# Main-v5_1.net
KiCad netlist of a schematic drawn in EAGLE
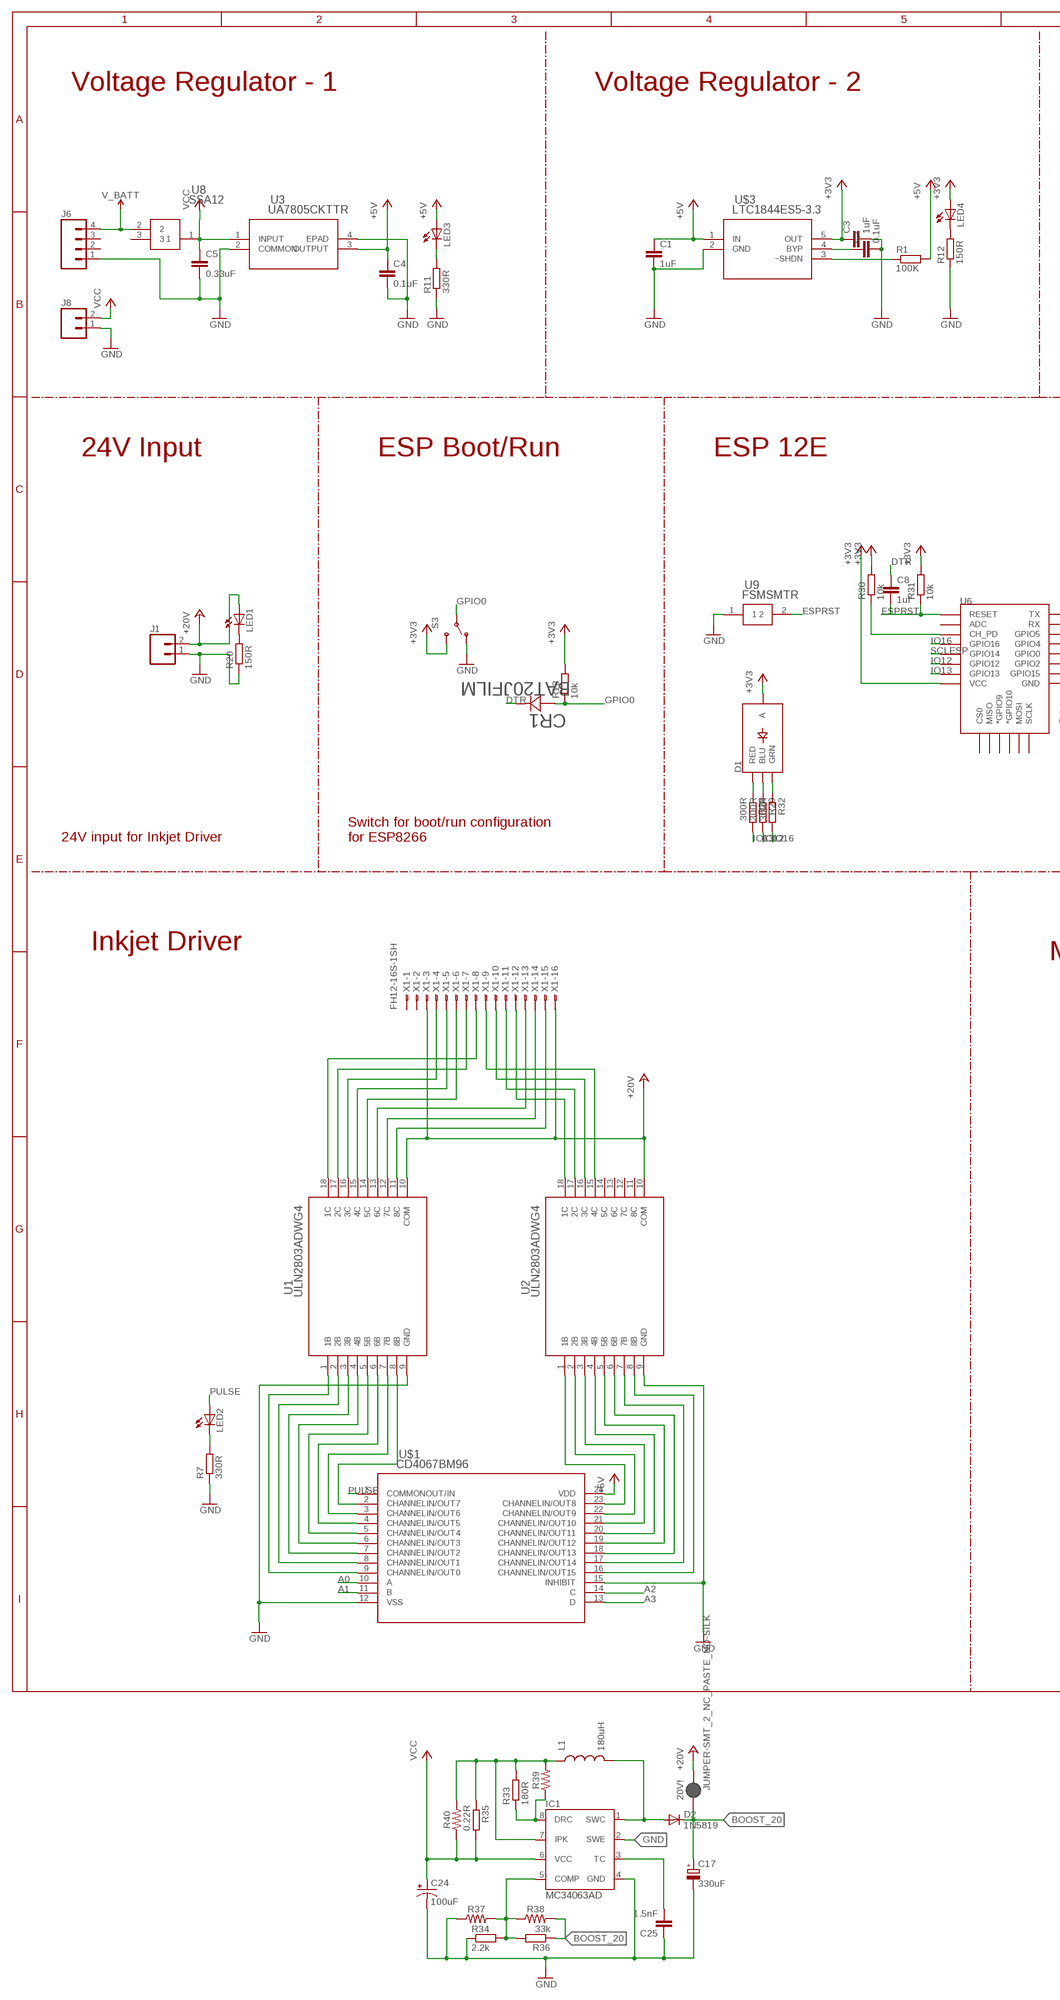
[diagram p0: schematic, sheet 1, part 1 of 2]
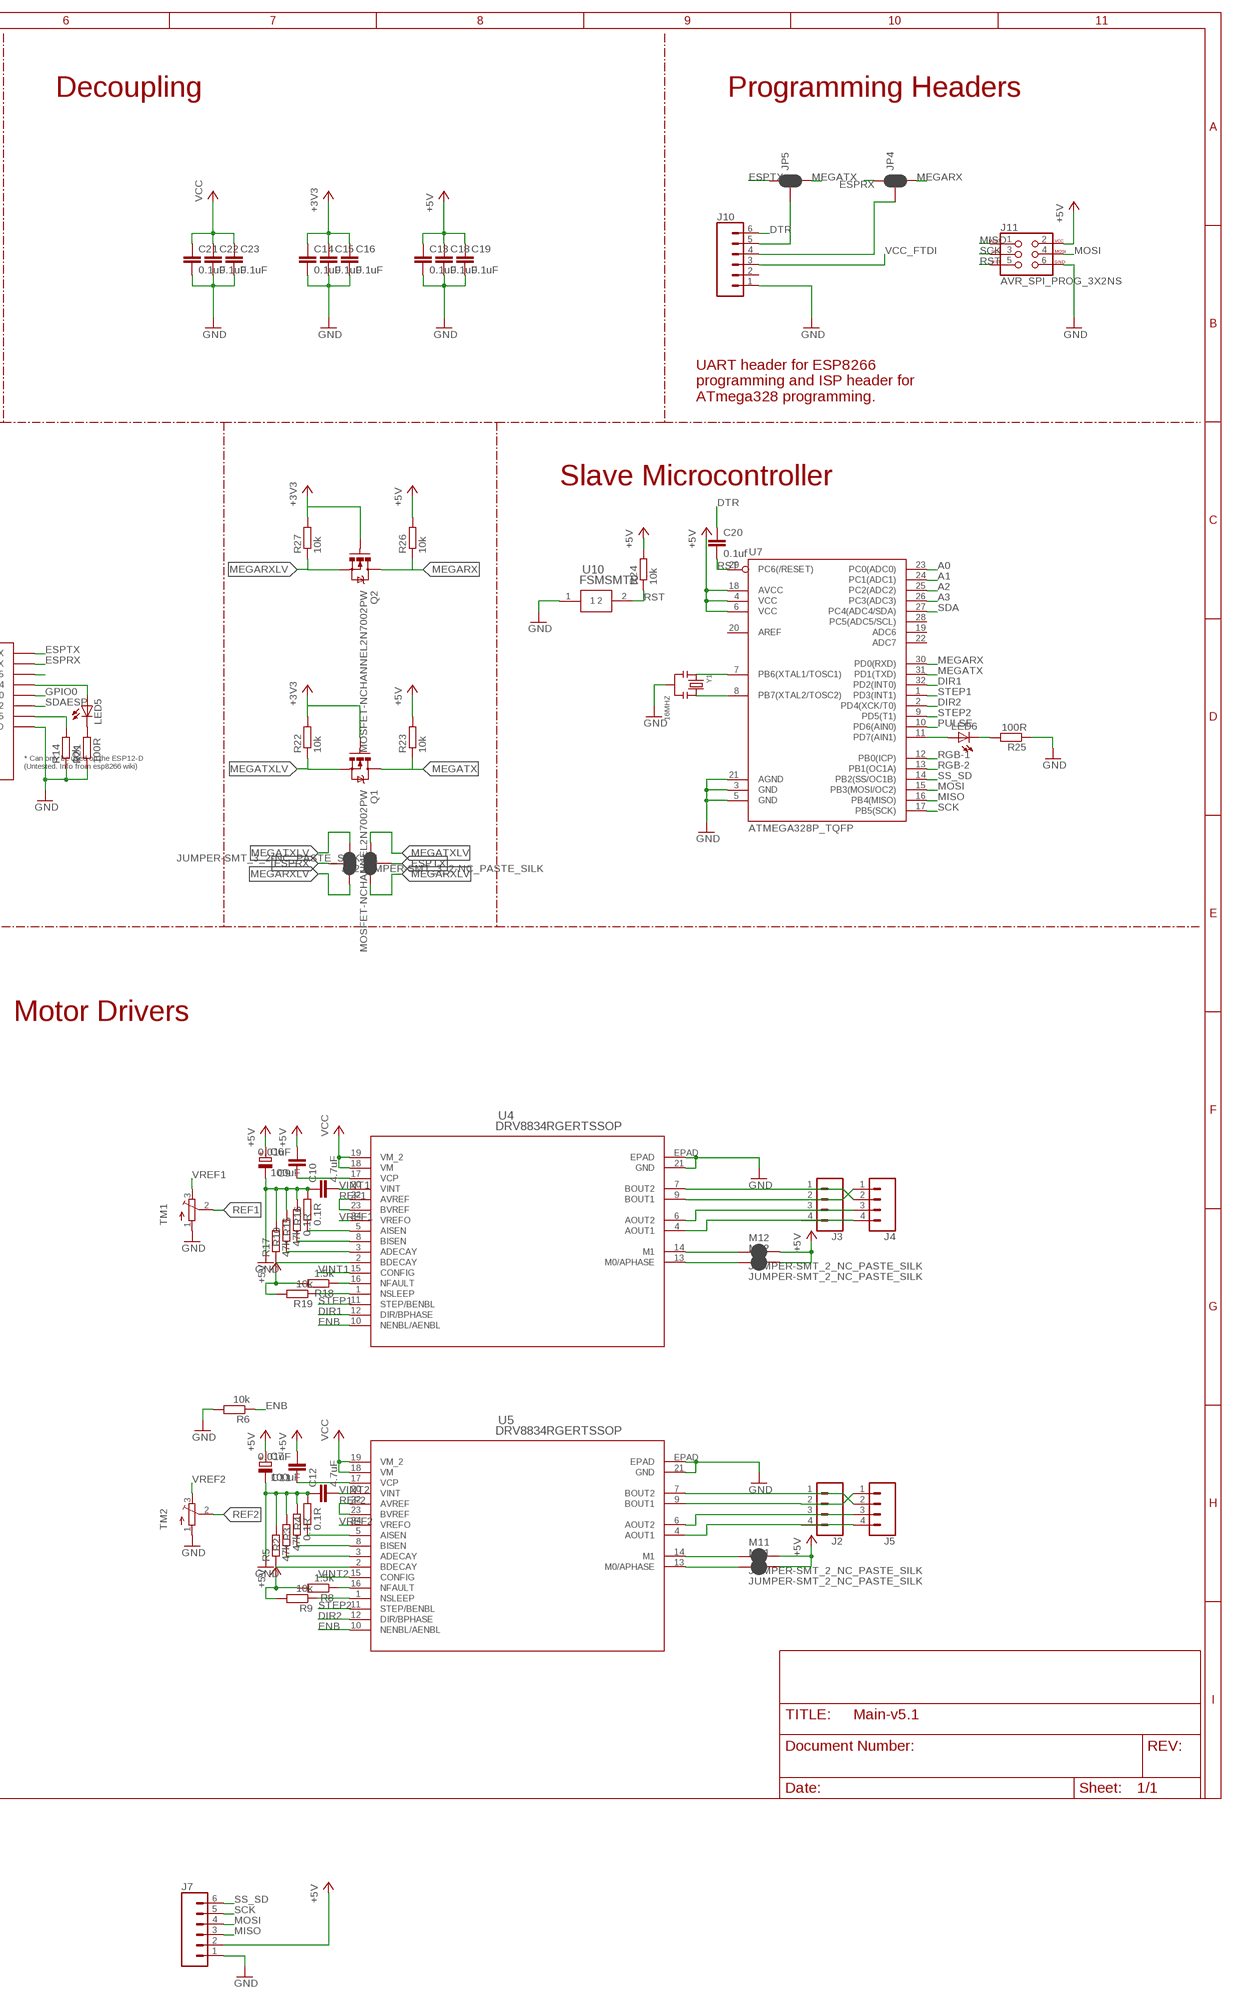
[diagram p1: schematic, sheet 1, part 2 of 2]

(export (version "E")
  (design (tool "Eeschema 10.0.6"))
  (components
    (comp (ref "20V!")
      (value "JUMPER-SMT_2_NC_PASTE_NO-SILK")
      (footprint "eagle-import:SMT-JUMPER_2_NC_PASTE_NO-SILK")
      (libsource (lib "eagle-import") (part "JUMPER-SMT_2_NC_PASTE_NO-SILK"))
    )
    (comp (ref "C1")
      (value "1uF")
      (footprint "eagle-import:C0603")
      (libsource (lib "eagle-import") (part "C-EUC0603"))
    )
    (comp (ref "C2")
      (value "0.1uF")
      (footprint "eagle-import:C0603")
      (libsource (lib "eagle-import") (part "C-EUC0603"))
    )
    (comp (ref "C3")
      (value "1uF")
      (footprint "eagle-import:C0603")
      (libsource (lib "eagle-import") (part "C-EUC0603"))
    )
    (comp (ref "C4")
      (value "0.1uF")
      (footprint "eagle-import:C0603")
      (libsource (lib "eagle-import") (part "C-EUC0603"))
    )
    (comp (ref "C5")
      (value "0.33uF")
      (footprint "eagle-import:C0603")
      (libsource (lib "eagle-import") (part "C-EUC0603"))
    )
    (comp (ref "C6")
      (value "100uF")
      (footprint "eagle-import:E5-5")
      (libsource (lib "eagle-import") (part "CPOL-EUE5-5"))
    )
    (comp (ref "C7")
      (value "100uF")
      (footprint "eagle-import:E5-5")
      (libsource (lib "eagle-import") (part "CPOL-EUE5-5"))
    )
    (comp (ref "C8")
      (value "1uf")
      (footprint "eagle-import:C0603")
      (libsource (lib "eagle-import") (part "resistor_348_C-EUC0603"))
    )
    (comp (ref "C9")
      (value "0.01uF")
      (footprint "eagle-import:C0603K")
      (libsource (lib "eagle-import") (part "resistor_348_C-EUC0603K"))
    )
    (comp (ref "C10")
      (value "4.7uF")
      (footprint "eagle-import:C0603K")
      (libsource (lib "eagle-import") (part "resistor_348_C-EUC0603K"))
    )
    (comp (ref "C11")
      (value "0.01uF")
      (footprint "eagle-import:C0603K")
      (libsource (lib "eagle-import") (part "resistor_348_C-EUC0603K"))
    )
    (comp (ref "C12")
      (value "4.7uF")
      (footprint "eagle-import:C0603K")
      (libsource (lib "eagle-import") (part "resistor_348_C-EUC0603K"))
    )
    (comp (ref "C13")
      (value "0.1uF")
      (footprint "eagle-import:C0603")
      (libsource (lib "eagle-import") (part "C-EUC0603"))
    )
    (comp (ref "C14")
      (value "0.1uF")
      (footprint "eagle-import:C0603")
      (libsource (lib "eagle-import") (part "C-EUC0603"))
    )
    (comp (ref "C15")
      (value "0.1uF")
      (footprint "eagle-import:C0603")
      (libsource (lib "eagle-import") (part "C-EUC0603"))
    )
    (comp (ref "C16")
      (value "0.1uF")
      (footprint "eagle-import:C0603")
      (libsource (lib "eagle-import") (part "C-EUC0603"))
    )
    (comp (ref "C17")
      (value "330uF")
      (footprint "eagle-import:153CLV-1010")
      (libsource (lib "eagle-import") (part "resistor_348_CPOL-EU153CLV-1010"))
    )
    (comp (ref "C18")
      (value "0.1uF")
      (footprint "eagle-import:C0603")
      (libsource (lib "eagle-import") (part "C-EUC0603"))
    )
    (comp (ref "C19")
      (value "0.1uF")
      (footprint "eagle-import:C0603")
      (libsource (lib "eagle-import") (part "C-EUC0603"))
    )
    (comp (ref "C20")
      (value "0.1uf")
      (footprint "eagle-import:C0603")
      (libsource (lib "eagle-import") (part "resistor_348_C-EUC0603"))
    )
    (comp (ref "C21")
      (value "0.1uF")
      (footprint "eagle-import:C0603")
      (libsource (lib "eagle-import") (part "C-EUC0603"))
    )
    (comp (ref "C22")
      (value "0.1uF")
      (footprint "eagle-import:C0603")
      (libsource (lib "eagle-import") (part "C-EUC0603"))
    )
    (comp (ref "C23")
      (value "0.1uF")
      (footprint "eagle-import:C0603")
      (libsource (lib "eagle-import") (part "C-EUC0603"))
    )
    (comp (ref "C24")
      (value "100uF")
      (footprint "eagle-import:CPOL-RADIAL-5MM-10MM")
      (libsource (lib "eagle-import") (part "1000UF-RADIAL-5MM-25V-20%"))
    )
    (comp (ref "C25")
      (value "1.5nF")
      (footprint "eagle-import:C0603K")
      (libsource (lib "eagle-import") (part "resistor_348_C-EUC0603K"))
    )
    (comp (ref "CR1")
      (value "BAT20JFILM")
      (footprint "eagle-import:SOD-323")
      (libsource (lib "eagle-import") (part "BAT20JFILM"))
    )
    (comp (ref "D1")
      (value "LED-RGB-CASMD")
      (footprint "eagle-import:LED-TRICOLOR-SMD")
      (libsource (lib "eagle-import") (part "LED-RGB-CASMD"))
    )
    (comp (ref "D2")
      (value "1N5819")
      (footprint "eagle-import:SOD123")
      (libsource (lib "eagle-import") (part "1N5819"))
    )
    (comp (ref "IC1")
      (value "MC34063AD")
      (footprint "eagle-import:SO08")
      (fields (field (name "MF") "ON Semiconductor") (field (name "MP") "MC34063A"))
      (libsource (lib "eagle-import") (part "MC34063AD"))
    )
    (comp (ref "J1")
      (value "CONN_02")
      (footprint "eagle-import:1X02")
      (libsource (lib "eagle-import") (part "SparkFun-Connectors_513_CONN_02"))
    )
    (comp (ref "J2")
      (value "CONN_04")
      (footprint "eagle-import:1X04")
      (libsource (lib "eagle-import") (part "CONN_04"))
    )
    (comp (ref "J3")
      (value "CONN_04")
      (footprint "eagle-import:1X04")
      (libsource (lib "eagle-import") (part "CONN_04"))
    )
    (comp (ref "J4")
      (value "CONN_04")
      (footprint "eagle-import:1X04")
      (libsource (lib "eagle-import") (part "CONN_04"))
    )
    (comp (ref "J5")
      (value "CONN_04")
      (footprint "eagle-import:1X04")
      (libsource (lib "eagle-import") (part "CONN_04"))
    )
    (comp (ref "J6")
      (value "CONN_04")
      (footprint "eagle-import:1X04")
      (libsource (lib "eagle-import") (part "CONN_04"))
    )
    (comp (ref "J7")
      (value "CONN_06SILK_FEMALE_PTH")
      (footprint "eagle-import:1X06")
      (libsource (lib "eagle-import") (part "CONN_06SILK_FEMALE_PTH"))
    )
    (comp (ref "J8")
      (value "CONN_02")
      (footprint "eagle-import:1X02")
      (libsource (lib "eagle-import") (part "CONN_02"))
    )
    (comp (ref "J10")
      (value "CONN_06NO_SILK_NO_POP")
      (footprint "eagle-import:1X06_NO_SILK")
      (libsource (lib "eagle-import") (part "SparkFun-Connectors_513_CONN_06NO_SILK_NO_POP"))
    )
    (comp (ref "J11")
      (value "AVR_SPI_PROG_3X2NS")
      (footprint "eagle-import:2X3-NS")
      (libsource (lib "eagle-import") (part "AVR_SPI_PROG_3X2NS"))
    )
    (comp (ref "JP1")
      (value "JUMPER-SMT_3_2-NC_PASTE_SILK")
      (footprint "eagle-import:SMT-JUMPER_3_2-NC_PASTE_SILK")
      (libsource (lib "eagle-import") (part "JUMPER-SMT_3_2-NC_PASTE_SILK"))
    )
    (comp (ref "JP2")
      (value "JUMPER-SMT_3_2-NC_PASTE_SILK")
      (footprint "eagle-import:SMT-JUMPER_3_2-NC_PASTE_SILK")
      (libsource (lib "eagle-import") (part "JUMPER-SMT_3_2-NC_PASTE_SILK"))
    )
    (comp (ref "JP4")
      (value "JUMPER-SMT_3_2-NC_PASTE_SILK")
      (footprint "eagle-import:SMT-JUMPER_3_2-NC_PASTE_SILK")
      (libsource (lib "eagle-import") (part "JUMPER-SMT_3_2-NC_PASTE_SILK"))
    )
    (comp (ref "JP5")
      (value "JUMPER-SMT_3_2-NC_PASTE_SILK")
      (footprint "eagle-import:SMT-JUMPER_3_2-NC_PASTE_SILK")
      (libsource (lib "eagle-import") (part "JUMPER-SMT_3_2-NC_PASTE_SILK"))
    )
    (comp (ref "L1")
      (value "180uH")
      (footprint "eagle-import:CR54")
      (libsource (lib "eagle-import") (part "INDUCTORCR54"))
    )
    (comp (ref "LED1")
      (value "LEDSML0603")
      (footprint "eagle-import:SML0603")
      (libsource (lib "eagle-import") (part "LEDSML0603"))
    )
    (comp (ref "LED2")
      (value "LEDSML0603")
      (footprint "eagle-import:SML0603")
      (libsource (lib "eagle-import") (part "LEDSML0603"))
    )
    (comp (ref "LED3")
      (value "LEDSML0603")
      (footprint "eagle-import:SML0603")
      (libsource (lib "eagle-import") (part "LEDSML0603"))
    )
    (comp (ref "LED4")
      (value "LEDSML0603")
      (footprint "eagle-import:SML0603")
      (libsource (lib "eagle-import") (part "LEDSML0603"))
    )
    (comp (ref "LED5")
      (value "LEDSML0603")
      (footprint "eagle-import:SML0603")
      (libsource (lib "eagle-import") (part "LEDSML0603"))
    )
    (comp (ref "LED6")
      (value "LEDSML0603")
      (footprint "eagle-import:SML0603")
      (libsource (lib "eagle-import") (part "LEDSML0603"))
    )
    (comp (ref "M01")
      (value "JUMPER-SMT_2_NC_PASTE_SILK")
      (footprint "eagle-import:SMT-JUMPER_2_NC_PASTE_SILK")
      (libsource (lib "eagle-import") (part "JUMPER-SMT_2_NC_PASTE_SILK"))
    )
    (comp (ref "M02")
      (value "JUMPER-SMT_2_NC_PASTE_SILK")
      (footprint "eagle-import:SMT-JUMPER_2_NC_PASTE_SILK")
      (libsource (lib "eagle-import") (part "JUMPER-SMT_2_NC_PASTE_SILK"))
    )
    (comp (ref "M11")
      (value "JUMPER-SMT_2_NC_PASTE_SILK")
      (footprint "eagle-import:SMT-JUMPER_2_NC_PASTE_SILK")
      (libsource (lib "eagle-import") (part "JUMPER-SMT_2_NC_PASTE_SILK"))
    )
    (comp (ref "M12")
      (value "JUMPER-SMT_2_NC_PASTE_SILK")
      (footprint "eagle-import:SMT-JUMPER_2_NC_PASTE_SILK")
      (libsource (lib "eagle-import") (part "JUMPER-SMT_2_NC_PASTE_SILK"))
    )
    (comp (ref "Q1")
      (value "MOSFET-NCHANNEL2N7002PW")
      (footprint "eagle-import:SOT323")
      (libsource (lib "eagle-import") (part "MOSFET-NCHANNEL2N7002PW"))
    )
    (comp (ref "Q2")
      (value "MOSFET-NCHANNEL2N7002PW")
      (footprint "eagle-import:SOT323")
      (libsource (lib "eagle-import") (part "MOSFET-NCHANNEL2N7002PW"))
    )
    (comp (ref "R1")
      (value "100K")
      (footprint "eagle-import:R0603")
      (libsource (lib "eagle-import") (part "R-EU_R0603"))
    )
    (comp (ref "R2")
      (value "47k")
      (footprint "eagle-import:R0402")
      (libsource (lib "eagle-import") (part "resistor_348_R-EU_R0402"))
    )
    (comp (ref "R3")
      (value "0.1R")
      (footprint "eagle-import:R0402")
      (libsource (lib "eagle-import") (part "resistor_348_R-EU_R0402"))
    )
    (comp (ref "R4")
      (value "0.1R")
      (footprint "eagle-import:R0402")
      (libsource (lib "eagle-import") (part "resistor_348_R-EU_R0402"))
    )
    (comp (ref "R5")
      (value "47k")
      (footprint "eagle-import:R0402")
      (libsource (lib "eagle-import") (part "resistor_348_R-EU_R0402"))
    )
    (comp (ref "R6")
      (value "10k")
      (footprint "eagle-import:R0402")
      (libsource (lib "eagle-import") (part "resistor_348_R-EU_R0402"))
    )
    (comp (ref "R7")
      (value "330R")
      (footprint "eagle-import:R0603")
      (libsource (lib "eagle-import") (part "R-EU_R0603"))
    )
    (comp (ref "R8")
      (value "1.5k")
      (footprint "eagle-import:R0402")
      (libsource (lib "eagle-import") (part "resistor_348_R-EU_R0402"))
    )
    (comp (ref "R9")
      (value "10k")
      (footprint "eagle-import:R0402")
      (libsource (lib "eagle-import") (part "resistor_348_R-EU_R0402"))
    )
    (comp (ref "R10")
      (value "47k")
      (footprint "eagle-import:R0402")
      (libsource (lib "eagle-import") (part "resistor_348_R-EU_R0402"))
    )
    (comp (ref "R11")
      (value "330R")
      (footprint "eagle-import:R0603")
      (libsource (lib "eagle-import") (part "R-EU_R0603"))
    )
    (comp (ref "R12")
      (value "150R")
      (footprint "eagle-import:R0603")
      (libsource (lib "eagle-import") (part "R-EU_R0603"))
    )
    (comp (ref "R13")
      (value "10k")
      (footprint "eagle-import:R0603")
      (libsource (lib "eagle-import") (part "R-EU_R0603"))
    )
    (comp (ref "R14")
      (value "10k")
      (footprint "eagle-import:R0603")
      (libsource (lib "eagle-import") (part "R-EU_R0603"))
    )
    (comp (ref "R15")
      (value "0.1R")
      (footprint "eagle-import:R0402")
      (libsource (lib "eagle-import") (part "resistor_348_R-EU_R0402"))
    )
    (comp (ref "R16")
      (value "0.1R")
      (footprint "eagle-import:R0402")
      (libsource (lib "eagle-import") (part "resistor_348_R-EU_R0402"))
    )
    (comp (ref "R17")
      (value "47k")
      (footprint "eagle-import:R0402")
      (libsource (lib "eagle-import") (part "resistor_348_R-EU_R0402"))
    )
    (comp (ref "R18")
      (value "1.5k")
      (footprint "eagle-import:R0402")
      (libsource (lib "eagle-import") (part "resistor_348_R-EU_R0402"))
    )
    (comp (ref "R19")
      (value "10k")
      (footprint "eagle-import:R0402")
      (libsource (lib "eagle-import") (part "resistor_348_R-EU_R0402"))
    )
    (comp (ref "R20")
      (value "150R")
      (footprint "eagle-import:R0603")
      (libsource (lib "eagle-import") (part "R-EU_R0603"))
    )
    (comp (ref "R21")
      (value "100R")
      (footprint "eagle-import:R0603")
      (libsource (lib "eagle-import") (part "R-EU_R0603"))
    )
    (comp (ref "R22")
      (value "10k")
      (footprint "eagle-import:R0603")
      (libsource (lib "eagle-import") (part "R-EU_R0603"))
    )
    (comp (ref "R23")
      (value "10k")
      (footprint "eagle-import:R0603")
      (libsource (lib "eagle-import") (part "R-EU_R0603"))
    )
    (comp (ref "R24")
      (value "10k")
      (footprint "eagle-import:R0603")
      (libsource (lib "eagle-import") (part "R-EU_R0603"))
    )
    (comp (ref "R25")
      (value "100R")
      (footprint "eagle-import:R0603")
      (libsource (lib "eagle-import") (part "R-EU_R0603"))
    )
    (comp (ref "R26")
      (value "10k")
      (footprint "eagle-import:R0603")
      (libsource (lib "eagle-import") (part "R-EU_R0603"))
    )
    (comp (ref "R27")
      (value "10k")
      (footprint "eagle-import:R0603")
      (libsource (lib "eagle-import") (part "R-EU_R0603"))
    )
    (comp (ref "R28")
      (value "300R")
      (footprint "eagle-import:R0603")
      (libsource (lib "eagle-import") (part "R-EU_R0603"))
    )
    (comp (ref "R29")
      (value "300R")
      (footprint "eagle-import:R0603")
      (libsource (lib "eagle-import") (part "R-EU_R0603"))
    )
    (comp (ref "R30")
      (value "10k")
      (footprint "eagle-import:R0603")
      (libsource (lib "eagle-import") (part "R-EU_R0603"))
    )
    (comp (ref "R31")
      (value "10k")
      (footprint "eagle-import:R0603")
      (libsource (lib "eagle-import") (part "R-EU_R0603"))
    )
    (comp (ref "R32")
      (value "300R")
      (footprint "eagle-import:R0603")
      (libsource (lib "eagle-import") (part "R-EU_R0603"))
    )
    (comp (ref "R33")
      (value "180R")
      (footprint "eagle-import:R0603")
      (libsource (lib "eagle-import") (part "R-EU_R0603"))
    )
    (comp (ref "R34")
      (value "2.2k")
      (footprint "eagle-import:R0603")
      (libsource (lib "eagle-import") (part "R-EU_R0603"))
    )
    (comp (ref "R35")
      (value "0.22R")
      (footprint "eagle-import:R0603")
      (libsource (lib "eagle-import") (part "R-EU_R0603"))
    )
    (comp (ref "R36")
      (value "33k")
      (footprint "eagle-import:R0603")
      (libsource (lib "eagle-import") (part "R-EU_R0603"))
    )
    (comp (ref "R37")
      (value "RESISTORAXIAL-0.3")
      (footprint "eagle-import:AXIAL-0.3")
      (libsource (lib "eagle-import") (part "RESISTORAXIAL-0.3"))
    )
    (comp (ref "R38")
      (value "RESISTORAXIAL-0.3")
      (footprint "eagle-import:AXIAL-0.3")
      (libsource (lib "eagle-import") (part "RESISTORAXIAL-0.3"))
    )
    (comp (ref "R39")
      (value "RESISTORAXIAL-0.3")
      (footprint "eagle-import:AXIAL-0.3")
      (libsource (lib "eagle-import") (part "RESISTORAXIAL-0.3"))
    )
    (comp (ref "R40")
      (value "RESISTORAXIAL-0.3")
      (footprint "eagle-import:AXIAL-0.3")
      (libsource (lib "eagle-import") (part "RESISTORAXIAL-0.3"))
    )
    (comp (ref "S3")
      (value "SWITCH-SPDT-SMD-A")
      (footprint "eagle-import:SWITCH-SPST-SMD-A")
      (libsource (lib "eagle-import") (part "SWITCH-SPDT-SMD-A"))
    )
    (comp (ref "TM1")
      (value "TRIMPOTTC33X")
      (footprint "eagle-import:TC33X")
      (libsource (lib "eagle-import") (part "TRIMPOTTC33X"))
    )
    (comp (ref "TM2")
      (value "TRIMPOTTC33X")
      (footprint "eagle-import:TC33X")
      (libsource (lib "eagle-import") (part "TRIMPOTTC33X"))
    )
    (comp (ref "U$1")
      (value "CD4067BM96")
      (footprint "eagle-import:DW24")
      (fields (field (name "MANUFACTURER_PART_NUMBER") "CD4067B_DW_24"))
      (libsource (lib "eagle-import") (part "CD4067BM96"))
    )
    (comp (ref "U$3")
      (value "LTC1844ES5-3.3")
      (footprint "eagle-import:TSOT-23_S5")
      (libsource (lib "eagle-import") (part "LTC1844ES5-3.3"))
    )
    (comp (ref "U1")
      (value "ULN2803ADWG4")
      (footprint "eagle-import:DW18")
      (libsource (lib "eagle-import") (part "ULN2803ADWG4"))
    )
    (comp (ref "U2")
      (value "ULN2803ADWG4")
      (footprint "eagle-import:DW18")
      (libsource (lib "eagle-import") (part "ULN2803ADWG4"))
    )
    (comp (ref "U3")
      (value "UA7805CKTTR")
      (footprint "eagle-import:KTT3_6P22X6P6")
      (libsource (lib "eagle-import") (part "UA7805CKTTR"))
    )
    (comp (ref "U4")
      (value "DRV8834RGERTSSOP")
      (footprint "eagle-import:PWP_24")
      (libsource (lib "eagle-import") (part "DRV8834RGERTSSOP"))
    )
    (comp (ref "U5")
      (value "DRV8834RGERTSSOP")
      (footprint "eagle-import:PWP_24")
      (libsource (lib "eagle-import") (part "DRV8834RGERTSSOP"))
    )
    (comp (ref "U6")
      (value "ESP12ESMD")
      (footprint "eagle-import:ESP12E-SMD")
      (libsource (lib "eagle-import") (part "ESP12ESMD"))
    )
    (comp (ref "U7")
      (value "ATMEGA328P_TQFP")
      (footprint "eagle-import:TQFP32-08")
      (libsource (lib "eagle-import") (part "ATMEGA328P_TQFP"))
    )
    (comp (ref "U8")
      (value "SSA12")
      (footprint "eagle-import:SWSIP3-P98")
      (libsource (lib "eagle-import") (part "SSA12"))
    )
    (comp (ref "U9")
      (value "FSMSMTR")
      (footprint "eagle-import:SWITCH_FSMSMTR")
      (libsource (lib "eagle-import") (part "FSMSMTR"))
    )
    (comp (ref "U10")
      (value "FSMSMTR")
      (footprint "eagle-import:SWITCH_FSMSMTR")
      (libsource (lib "eagle-import") (part "FSMSMTR"))
    )
    (comp (ref "X1")
      (value "FH12-16S-1SH")
      (footprint "eagle-import:FH12-16S-1SH")
      (libsource (lib "eagle-import") (part "FH12-16S-1SH"))
    )
    (comp (ref "Y1")
      (value "16MHZ")
      (footprint "eagle-import:X3-SMD-3.6X1.3X0.8MM")
      (fields (field (name "MPN") "CSTCE16M0V53-R0"))
      (libsource (lib "eagle-import") (part "SMD-RESONATOR-16MHZ-15PF-0.5%-40R(3P-3.2X1.3MM)"))
    )
  )
  (nets
    (net (code "1") (name "+3V3") (class "Default")
      (node (ref "C14") (pin "1") (pinfunction "1_1") (pintype "passive"))
      (node (ref "C15") (pin "1") (pinfunction "1_1") (pintype "passive"))
      (node (ref "C16") (pin "1") (pinfunction "1_1") (pintype "passive"))
      (node (ref "C3") (pin "1") (pinfunction "1_1") (pintype "passive"))
      (node (ref "D1") (pin "A") (pinfunction "A_A") (pintype "bidirectional"))
      (node (ref "LED4") (pin "A") (pinfunction "A_A") (pintype "passive"))
      (node (ref "Q1") (pin "1") (pinfunction "G_1") (pintype "passive"))
      (node (ref "Q2") (pin "1") (pinfunction "G_1") (pintype "passive"))
      (node (ref "R13") (pin "2") (pinfunction "2_2") (pintype "passive"))
      (node (ref "R22") (pin "2") (pinfunction "2_2") (pintype "passive"))
      (node (ref "R27") (pin "2") (pinfunction "2_2") (pintype "passive"))
      (node (ref "R30") (pin "2") (pinfunction "2_2") (pintype "passive"))
      (node (ref "R31") (pin "2") (pinfunction "2_2") (pintype "passive"))
      (node (ref "S3") (pin "3") (pinfunction "S_3") (pintype "passive"))
      (node (ref "U$3") (pin "5") (pinfunction "OUT_5") (pintype "passive"))
      (node (ref "U6") (pin "VCC") (pinfunction "VCC_VCC") (pintype "bidirectional"))
    )
    (net (code "2") (name "+5V") (class "Default")
      (node (ref "C1") (pin "1") (pinfunction "1_1") (pintype "passive"))
      (node (ref "C11") (pin "2") (pinfunction "2_2") (pintype "passive"))
      (node (ref "C13") (pin "1") (pinfunction "1_1") (pintype "passive"))
      (node (ref "C18") (pin "1") (pinfunction "1_1") (pintype "passive"))
      (node (ref "C19") (pin "1") (pinfunction "1_1") (pintype "passive"))
      (node (ref "C4") (pin "1") (pinfunction "1_1") (pintype "passive"))
      (node (ref "C6") (pin "+") (pinfunction "+_+") (pintype "passive"))
      (node (ref "C7") (pin "+") (pinfunction "+_+") (pintype "passive"))
      (node (ref "C9") (pin "2") (pinfunction "2_2") (pintype "passive"))
      (node (ref "J11") (pin "2") (pinfunction "2_2") (pintype "passive"))
      (node (ref "J7") (pin "2") (pinfunction "2_2") (pintype "passive"))
      (node (ref "LED3") (pin "A") (pinfunction "A_A") (pintype "passive"))
      (node (ref "M01") (pin "2") (pinfunction "2_2") (pintype "passive"))
      (node (ref "M02") (pin "2") (pinfunction "2_2") (pintype "passive"))
      (node (ref "M11") (pin "2") (pinfunction "2_2") (pintype "passive"))
      (node (ref "M12") (pin "2") (pinfunction "2_2") (pintype "passive"))
      (node (ref "R1") (pin "2") (pinfunction "2_2") (pintype "passive"))
      (node (ref "R18") (pin "2") (pinfunction "2_2") (pintype "passive"))
      (node (ref "R19") (pin "2") (pinfunction "2_2") (pintype "passive"))
      (node (ref "R23") (pin "2") (pinfunction "2_2") (pintype "passive"))
      (node (ref "R24") (pin "2") (pinfunction "2_2") (pintype "passive"))
      (node (ref "R26") (pin "2") (pinfunction "2_2") (pintype "passive"))
      (node (ref "R8") (pin "2") (pinfunction "2_2") (pintype "passive"))
      (node (ref "R9") (pin "2") (pinfunction "2_2") (pintype "passive"))
      (node (ref "U$1") (pin "24") (pinfunction "VDD_24") (pintype "power_in"))
      (node (ref "U$3") (pin "1") (pinfunction "IN_1") (pintype "passive"))
      (node (ref "U3") (pin "3") (pinfunction "OUTPUT_3") (pintype "output"))
      (node (ref "U7") (pin "18") (pinfunction "AVCC_18") (pintype "bidirectional"))
      (node (ref "U7") (pin "4") (pinfunction "VCC_4") (pintype "bidirectional"))
      (node (ref "U7") (pin "6") (pinfunction "VCC_6") (pintype "bidirectional"))
    )
    (net (code "3") (name "+20V") (class "Default")
      (node (ref "20V!") (pin "2") (pinfunction "2_2") (pintype "passive"))
      (node (ref "J1") (pin "2") (pinfunction "2_2") (pintype "passive"))
      (node (ref "LED1") (pin "A") (pinfunction "A_A") (pintype "passive"))
      (node (ref "U1") (pin "10") (pinfunction "COM_10") (pintype "passive"))
      (node (ref "U2") (pin "10") (pinfunction "COM_10") (pintype "passive"))
      (node (ref "X1") (pin "16") (pinfunction "1_16") (pintype "passive"))
      (node (ref "X1") (pin "3") (pinfunction "1_3") (pintype "passive"))
    )
    (net (code "4") (name "/A0") (class "Default")
      (node (ref "U$1") (pin "10") (pinfunction "A_10") (pintype "passive"))
      (node (ref "U7") (pin "23") (pinfunction "PC0(ADC0)_23") (pintype "bidirectional"))
    )
    (net (code "5") (name "/A1") (class "Default")
      (node (ref "U$1") (pin "11") (pinfunction "B_11") (pintype "passive"))
      (node (ref "U7") (pin "24") (pinfunction "PC1(ADC1)_24") (pintype "bidirectional"))
    )
    (net (code "6") (name "/A2") (class "Default")
      (node (ref "U$1") (pin "14") (pinfunction "C_14") (pintype "passive"))
      (node (ref "U7") (pin "25") (pinfunction "PC2(ADC2)_25") (pintype "bidirectional"))
    )
    (net (code "7") (name "/A3") (class "Default")
      (node (ref "U$1") (pin "13") (pinfunction "D_13") (pintype "passive"))
      (node (ref "U7") (pin "26") (pinfunction "PC3(ADC3)_26") (pintype "bidirectional"))
    )
    (net (code "8") (name "/DIR1") (class "Default")
      (node (ref "U4") (pin "12") (pinfunction "DIR/BPHASE_12") (pintype "input"))
      (node (ref "U7") (pin "32") (pinfunction "PD2(INT0)_32") (pintype "bidirectional"))
    )
    (net (code "9") (name "/DIR2") (class "Default")
      (node (ref "U5") (pin "12") (pinfunction "DIR/BPHASE_12") (pintype "input"))
      (node (ref "U7") (pin "2") (pinfunction "PD4(XCK/T0)_2") (pintype "bidirectional"))
    )
    (net (code "10") (name "/DTR") (class "Default")
      (node (ref "C20") (pin "1") (pinfunction "1_1") (pintype "passive"))
      (node (ref "C8") (pin "1") (pinfunction "1_1") (pintype "passive"))
      (node (ref "CR1") (pin "1") (pinfunction "11_1") (pintype "passive"))
      (node (ref "J10") (pin "6") (pinfunction "6_6") (pintype "passive"))
    )
    (net (code "11") (name "/ENB") (class "Default")
      (node (ref "R6") (pin "1") (pinfunction "1_1") (pintype "passive"))
      (node (ref "U4") (pin "10") (pinfunction "NENBL/AENBL_10") (pintype "input"))
      (node (ref "U5") (pin "10") (pinfunction "NENBL/AENBL_10") (pintype "input"))
    )
    (net (code "12") (name "/ESPRST") (class "Default")
      (node (ref "C8") (pin "2") (pinfunction "2_2") (pintype "passive"))
      (node (ref "R31") (pin "1") (pinfunction "1_1") (pintype "passive"))
      (node (ref "U6") (pin "RESET") (pinfunction "RESET_RESET") (pintype "bidirectional"))
      (node (ref "U9") (pin "2") (pinfunction "2_2") (pintype "passive"))
    )
    (net (code "13") (name "/GPIO0") (class "Default")
      (node (ref "CR1") (pin "2") (pinfunction "22_2") (pintype "passive"))
      (node (ref "R13") (pin "1") (pinfunction "1_1") (pintype "passive"))
      (node (ref "S3") (pin "2") (pinfunction "P_2") (pintype "passive"))
      (node (ref "U6") (pin "GPIO0") (pinfunction "GPIO0_GPIO0") (pintype "bidirectional"))
    )
    (net (code "14") (name "/IO12") (class "Default")
      (node (ref "R29") (pin "2") (pinfunction "2_2") (pintype "passive"))
      (node (ref "U6") (pin "GPIO12") (pinfunction "GPIO12_GPIO12") (pintype "bidirectional"))
    )
    (net (code "15") (name "/IO13") (class "Default")
      (node (ref "R28") (pin "2") (pinfunction "2_2") (pintype "passive"))
      (node (ref "U6") (pin "GPIO13") (pinfunction "GPIO13_GPIO13") (pintype "bidirectional"))
    )
    (net (code "16") (name "/IO16") (class "Default")
      (node (ref "R32") (pin "2") (pinfunction "2_2") (pintype "passive"))
      (node (ref "U6") (pin "GPIO16") (pinfunction "GPIO16_GPIO16") (pintype "bidirectional"))
    )
    (net (code "17") (name "/MISO") (class "Default")
      (node (ref "J11") (pin "1") (pinfunction "1_1") (pintype "passive"))
      (node (ref "J7") (pin "3") (pinfunction "3_3") (pintype "passive"))
      (node (ref "U7") (pin "16") (pinfunction "PB4(MISO)_16") (pintype "bidirectional"))
    )
    (net (code "18") (name "/MOSI") (class "Default")
      (node (ref "J11") (pin "4") (pinfunction "4_4") (pintype "passive"))
      (node (ref "J7") (pin "4") (pinfunction "4_4") (pintype "passive"))
      (node (ref "U7") (pin "15") (pinfunction "PB3(MOSI/OC2)_15") (pintype "bidirectional"))
    )
    (net (code "19") (name "/PULSE") (class "Default")
      (node (ref "LED2") (pin "A") (pinfunction "A_A") (pintype "passive"))
      (node (ref "U$1") (pin "1") (pinfunction "COMMONOUT/IN_1") (pintype "bidirectional"))
      (node (ref "U7") (pin "10") (pinfunction "PD6(AIN0)_10") (pintype "bidirectional"))
    )
    (net (code "20") (name "/RGB-1") (class "Default")
      (node (ref "U7") (pin "12") (pinfunction "PB0(ICP)_12") (pintype "bidirectional"))
    )
    (net (code "21") (name "/RGB-2") (class "Default")
      (node (ref "U7") (pin "13") (pinfunction "PB1(OC1A)_13") (pintype "bidirectional"))
    )
    (net (code "22") (name "/RST") (class "Default")
      (node (ref "C20") (pin "2") (pinfunction "2_2") (pintype "passive"))
      (node (ref "J11") (pin "5") (pinfunction "5_5") (pintype "passive"))
      (node (ref "R24") (pin "1") (pinfunction "1_1") (pintype "passive"))
      (node (ref "U10") (pin "2") (pinfunction "2_2") (pintype "passive"))
      (node (ref "U7") (pin "29") (pinfunction "PC6(/RESET)_29") (pintype "bidirectional"))
    )
    (net (code "23") (name "/SCK") (class "Default")
      (node (ref "J11") (pin "3") (pinfunction "3_3") (pintype "passive"))
      (node (ref "J7") (pin "5") (pinfunction "5_5") (pintype "passive"))
      (node (ref "U7") (pin "17") (pinfunction "PB5(SCK)_17") (pintype "bidirectional"))
    )
    (net (code "24") (name "/SCLESP") (class "Default")
      (node (ref "U6") (pin "GPIO14") (pinfunction "GPIO14_GPIO14") (pintype "bidirectional"))
    )
    (net (code "25") (name "/SDA") (class "Default")
      (node (ref "U7") (pin "27") (pinfunction "PC4(ADC4/SDA)_27") (pintype "bidirectional"))
    )
    (net (code "26") (name "/SDAESP") (class "Default")
      (node (ref "U6") (pin "GPIO2") (pinfunction "GPIO2_GPIO2") (pintype "bidirectional"))
    )
    (net (code "27") (name "/SS_SD") (class "Default")
      (node (ref "J7") (pin "6") (pinfunction "6_6") (pintype "passive"))
      (node (ref "U7") (pin "14") (pinfunction "PB2(SS/OC1B)_14") (pintype "bidirectional"))
    )
    (net (code "28") (name "/STEP1") (class "Default")
      (node (ref "U4") (pin "11") (pinfunction "STEP/BENBL_11") (pintype "input"))
      (node (ref "U7") (pin "1") (pinfunction "PD3(INT1)_1") (pintype "bidirectional"))
    )
    (net (code "29") (name "/STEP2") (class "Default")
      (node (ref "U5") (pin "11") (pinfunction "STEP/BENBL_11") (pintype "input"))
      (node (ref "U7") (pin "9") (pinfunction "PD5(T1)_9") (pintype "bidirectional"))
    )
    (net (code "30") (name "/VCC_FTDI") (class "Default")
      (node (ref "J10") (pin "3") (pinfunction "3_3") (pintype "passive"))
    )
    (net (code "31") (name "/VINT1") (class "Default")
      (node (ref "C10") (pin "2") (pinfunction "2_2") (pintype "passive"))
      (node (ref "U4") (pin "15") (pinfunction "CONFIG_15") (pintype "input"))
      (node (ref "U4") (pin "20") (pinfunction "VINT_20") (pintype "passive"))
    )
    (net (code "32") (name "/VINT2") (class "Default")
      (node (ref "C12") (pin "2") (pinfunction "2_2") (pintype "passive"))
      (node (ref "U5") (pin "15") (pinfunction "CONFIG_15") (pintype "input"))
      (node (ref "U5") (pin "20") (pinfunction "VINT_20") (pintype "passive"))
    )
    (net (code "33") (name "/VREF1") (class "Default")
      (node (ref "TM1") (pin "3") (pinfunction "E_3") (pintype "passive"))
      (node (ref "U4") (pin "24") (pinfunction "VREFO_24") (pintype "output"))
    )
    (net (code "34") (name "/VREF2") (class "Default")
      (node (ref "TM2") (pin "3") (pinfunction "E_3") (pintype "passive"))
      (node (ref "U5") (pin "24") (pinfunction "VREFO_24") (pintype "output"))
    )
    (net (code "35") (name "BOOST_20") (class "Default")
      (node (ref "20V!") (pin "1") (pinfunction "1_1") (pintype "passive"))
      (node (ref "C17") (pin "+") (pinfunction "+_+") (pintype "passive"))
      (node (ref "D2") (pin "C") (pinfunction "C_C") (pintype "passive"))
      (node (ref "R36") (pin "1") (pinfunction "1_1") (pintype "passive"))
      (node (ref "R38") (pin "P$2") (pinfunction "2_P$2") (pintype "passive"))
    )
    (net (code "36") (name "ESPRX") (class "Default")
      (node (ref "JP1") (pin "2") (pinfunction "2_2") (pintype "passive"))
      (node (ref "JP4") (pin "1") (pinfunction "1_1") (pintype "passive"))
      (node (ref "U6") (pin "RXD0") (pinfunction "RX_RXD0") (pintype "bidirectional"))
    )
    (net (code "37") (name "ESPTX") (class "Default")
      (node (ref "JP2") (pin "2") (pinfunction "2_2") (pintype "passive"))
      (node (ref "JP5") (pin "1") (pinfunction "1_1") (pintype "passive"))
      (node (ref "U6") (pin "TXD0") (pinfunction "TX_TXD0") (pintype "bidirectional"))
    )
    (net (code "38") (name "GND") (class "Default")
      (node (ref "C1") (pin "2") (pinfunction "2_2") (pintype "passive"))
      (node (ref "C10") (pin "1") (pinfunction "1_1") (pintype "passive"))
      (node (ref "C12") (pin "1") (pinfunction "1_1") (pintype "passive"))
      (node (ref "C13") (pin "2") (pinfunction "2_2") (pintype "passive"))
      (node (ref "C14") (pin "2") (pinfunction "2_2") (pintype "passive"))
      (node (ref "C15") (pin "2") (pinfunction "2_2") (pintype "passive"))
      (node (ref "C16") (pin "2") (pinfunction "2_2") (pintype "passive"))
      (node (ref "C17") (pin "-") (pinfunction "-_-") (pintype "passive"))
      (node (ref "C18") (pin "2") (pinfunction "2_2") (pintype "passive"))
      (node (ref "C19") (pin "2") (pinfunction "2_2") (pintype "passive"))
      (node (ref "C2") (pin "2") (pinfunction "2_2") (pintype "passive"))
      (node (ref "C21") (pin "2") (pinfunction "2_2") (pintype "passive"))
      (node (ref "C22") (pin "2") (pinfunction "2_2") (pintype "passive"))
      (node (ref "C23") (pin "2") (pinfunction "2_2") (pintype "passive"))
      (node (ref "C24") (pin "-") (pinfunction "-_-") (pintype "passive"))
      (node (ref "C25") (pin "1") (pinfunction "1_1") (pintype "passive"))
      (node (ref "C3") (pin "2") (pinfunction "2_2") (pintype "passive"))
      (node (ref "C4") (pin "2") (pinfunction "2_2") (pintype "passive"))
      (node (ref "C5") (pin "2") (pinfunction "2_2") (pintype "passive"))
      (node (ref "C6") (pin "-") (pinfunction "-_-") (pintype "passive"))
      (node (ref "C7") (pin "-") (pinfunction "-_-") (pintype "passive"))
      (node (ref "IC1") (pin "2") (pinfunction "SWE_2") (pintype "bidirectional"))
      (node (ref "IC1") (pin "4") (pinfunction "GND_4") (pintype "power_in"))
      (node (ref "J1") (pin "1") (pinfunction "1_1") (pintype "passive"))
      (node (ref "J10") (pin "1") (pinfunction "1_1") (pintype "passive"))
      (node (ref "J11") (pin "6") (pinfunction "6_6") (pintype "passive"))
      (node (ref "J6") (pin "1") (pinfunction "1_1") (pintype "passive"))
      (node (ref "J7") (pin "1") (pinfunction "1_1") (pintype "passive"))
      (node (ref "J8") (pin "1") (pinfunction "1_1") (pintype "passive"))
      (node (ref "R10") (pin "2") (pinfunction "2_2") (pintype "passive"))
      (node (ref "R11") (pin "1") (pinfunction "1_1") (pintype "passive"))
      (node (ref "R12") (pin "1") (pinfunction "1_1") (pintype "passive"))
      (node (ref "R14") (pin "1") (pinfunction "1_1") (pintype "passive"))
      (node (ref "R15") (pin "2") (pinfunction "2_2") (pintype "passive"))
      (node (ref "R16") (pin "2") (pinfunction "2_2") (pintype "passive"))
      (node (ref "R17") (pin "2") (pinfunction "2_2") (pintype "passive"))
      (node (ref "R2") (pin "2") (pinfunction "2_2") (pintype "passive"))
      (node (ref "R20") (pin "1") (pinfunction "1_1") (pintype "passive"))
      (node (ref "R21") (pin "1") (pinfunction "1_1") (pintype "passive"))
      (node (ref "R25") (pin "1") (pinfunction "1_1") (pintype "passive"))
      (node (ref "R3") (pin "2") (pinfunction "2_2") (pintype "passive"))
      (node (ref "R34") (pin "1") (pinfunction "1_1") (pintype "passive"))
      (node (ref "R37") (pin "P$1") (pinfunction "1_P$1") (pintype "passive"))
      (node (ref "R4") (pin "2") (pinfunction "2_2") (pintype "passive"))
      (node (ref "R5") (pin "2") (pinfunction "2_2") (pintype "passive"))
      (node (ref "R6") (pin "2") (pinfunction "2_2") (pintype "passive"))
      (node (ref "R7") (pin "1") (pinfunction "1_1") (pintype "passive"))
      (node (ref "S3") (pin "1") (pinfunction "O_1") (pintype "passive"))
      (node (ref "TM1") (pin "1") (pinfunction "A_1") (pintype "passive"))
      (node (ref "TM2") (pin "1") (pinfunction "A_1") (pintype "passive"))
      (node (ref "U$1") (pin "12") (pinfunction "VSS_12") (pintype "power_in"))
      (node (ref "U$1") (pin "15") (pinfunction "INHIBIT_15") (pintype "passive"))
      (node (ref "U$3") (pin "2") (pinfunction "GND_2") (pintype "passive"))
      (node (ref "U1") (pin "9") (pinfunction "GND_9") (pintype "passive"))
      (node (ref "U10") (pin "1") (pinfunction "1_1") (pintype "passive"))
      (node (ref "U2") (pin "9") (pinfunction "GND_9") (pintype "passive"))
      (node (ref "U3") (pin "2") (pinfunction "COMMON_2") (pintype "power_in"))
      (node (ref "U3") (pin "4") (pinfunction "EPAD_4") (pintype "passive"))
      (node (ref "U4") (pin "21") (pinfunction "GND_21") (pintype "power_in"))
      (node (ref "U4") (pin "EPAD") (pinfunction "EPAD_EPAD") (pintype "passive"))
      (node (ref "U5") (pin "21") (pinfunction "GND_21") (pintype "power_in"))
      (node (ref "U5") (pin "EPAD") (pinfunction "EPAD_EPAD") (pintype "passive"))
      (node (ref "U6") (pin "GND") (pinfunction "GND_GND") (pintype "bidirectional"))
      (node (ref "U7") (pin "21") (pinfunction "AGND_21") (pintype "bidirectional"))
      (node (ref "U7") (pin "3") (pinfunction "GND_3") (pintype "bidirectional"))
      (node (ref "U7") (pin "5") (pinfunction "GND_5") (pintype "bidirectional"))
      (node (ref "U9") (pin "1") (pinfunction "1_1") (pintype "passive"))
      (node (ref "Y1") (pin "2") (pinfunction "2_2") (pintype "passive"))
    )
    (net (code "39") (name "MEGARX") (class "Default")
      (node (ref "JP4") (pin "3") (pinfunction "3_3") (pintype "passive"))
      (node (ref "Q2") (pin "3") (pinfunction "D_3") (pintype "passive"))
      (node (ref "R26") (pin "1") (pinfunction "1_1") (pintype "passive"))
      (node (ref "U7") (pin "30") (pinfunction "PD0(RXD)_30") (pintype "bidirectional"))
    )
    (net (code "40") (name "MEGARXLV") (class "Default")
      (node (ref "JP1") (pin "3") (pinfunction "3_3") (pintype "passive"))
      (node (ref "JP2") (pin "1") (pinfunction "1_1") (pintype "passive"))
      (node (ref "Q2") (pin "2") (pinfunction "S_2") (pintype "passive"))
      (node (ref "R27") (pin "1") (pinfunction "1_1") (pintype "passive"))
    )
    (net (code "41") (name "MEGATX") (class "Default")
      (node (ref "JP5") (pin "3") (pinfunction "3_3") (pintype "passive"))
      (node (ref "Q1") (pin "3") (pinfunction "D_3") (pintype "passive"))
      (node (ref "R23") (pin "1") (pinfunction "1_1") (pintype "passive"))
      (node (ref "U7") (pin "31") (pinfunction "PD1(TXD)_31") (pintype "bidirectional"))
    )
    (net (code "42") (name "MEGATXLV") (class "Default")
      (node (ref "JP1") (pin "1") (pinfunction "1_1") (pintype "passive"))
      (node (ref "JP2") (pin "3") (pinfunction "3_3") (pintype "passive"))
      (node (ref "Q1") (pin "2") (pinfunction "S_2") (pintype "passive"))
      (node (ref "R22") (pin "1") (pinfunction "1_1") (pintype "passive"))
    )
    (net (code "43") (name "Net-(D1-BLU)") (class "Default")
      (node (ref "D1") (pin "B") (pinfunction "BLU_B") (pintype "bidirectional"))
      (node (ref "R29") (pin "1") (pinfunction "1_1") (pintype "passive"))
    )
    (net (code "44") (name "Net-(D1-GRN)") (class "Default")
      (node (ref "D1") (pin "G") (pinfunction "GRN_G") (pintype "bidirectional"))
      (node (ref "R32") (pin "1") (pinfunction "1_1") (pintype "passive"))
    )
    (net (code "45") (name "Net-(D1-RED)") (class "Default")
      (node (ref "D1") (pin "R") (pinfunction "RED_R") (pintype "bidirectional"))
      (node (ref "R28") (pin "1") (pinfunction "1_1") (pintype "passive"))
    )
    (net (code "46") (name "Net-(IC1-COMP)") (class "Default")
      (node (ref "IC1") (pin "5") (pinfunction "COMP_5") (pintype "input"))
      (node (ref "R34") (pin "2") (pinfunction "2_2") (pintype "passive"))
      (node (ref "R36") (pin "2") (pinfunction "2_2") (pintype "passive"))
      (node (ref "R37") (pin "P$2") (pinfunction "2_P$2") (pintype "passive"))
      (node (ref "R38") (pin "P$1") (pinfunction "1_P$1") (pintype "passive"))
    )
    (net (code "47") (name "Net-(IC1-DRC)") (class "Default")
      (node (ref "IC1") (pin "8") (pinfunction "DRC_8") (pintype "input"))
      (node (ref "R33") (pin "1") (pinfunction "1_1") (pintype "passive"))
      (node (ref "R39") (pin "P$1") (pinfunction "1_P$1") (pintype "passive"))
    )
    (net (code "48") (name "Net-(IC1-IPK)") (class "Default")
      (node (ref "IC1") (pin "7") (pinfunction "IPK_7") (pintype "input"))
      (node (ref "L1") (pin "P$1") (pinfunction "1_P$1") (pintype "passive"))
      (node (ref "R33") (pin "2") (pinfunction "2_2") (pintype "passive"))
      (node (ref "R35") (pin "1") (pinfunction "1_1") (pintype "passive"))
      (node (ref "R39") (pin "P$2") (pinfunction "2_P$2") (pintype "passive"))
      (node (ref "R40") (pin "P$2") (pinfunction "2_P$2") (pintype "passive"))
    )
    (net (code "49") (name "Net-(IC1-SWC)") (class "Default")
      (node (ref "D2") (pin "A") (pinfunction "A_A") (pintype "passive"))
      (node (ref "IC1") (pin "1") (pinfunction "SWC_1") (pintype "bidirectional"))
      (node (ref "L1") (pin "P$2") (pinfunction "2_P$2") (pintype "passive"))
    )
    (net (code "50") (name "Net-(IC1-TC)") (class "Default")
      (node (ref "C25") (pin "2") (pinfunction "2_2") (pintype "passive"))
      (node (ref "IC1") (pin "3") (pinfunction "TC_3") (pintype "passive"))
    )
    (net (code "51") (name "Net-(J10-Pad4)") (class "Default")
      (node (ref "J10") (pin "4") (pinfunction "4_4") (pintype "passive"))
      (node (ref "JP4") (pin "2") (pinfunction "2_2") (pintype "passive"))
    )
    (net (code "52") (name "Net-(J10-Pad5)") (class "Default")
      (node (ref "J10") (pin "5") (pinfunction "5_5") (pintype "passive"))
      (node (ref "JP5") (pin "2") (pinfunction "2_2") (pintype "passive"))
    )
    (net (code "53") (name "Net-(LED1-PadC)") (class "Default")
      (node (ref "LED1") (pin "C") (pinfunction "C_C") (pintype "passive"))
      (node (ref "R20") (pin "2") (pinfunction "2_2") (pintype "passive"))
    )
    (net (code "54") (name "Net-(LED2-PadC)") (class "Default")
      (node (ref "LED2") (pin "C") (pinfunction "C_C") (pintype "passive"))
      (node (ref "R7") (pin "2") (pinfunction "2_2") (pintype "passive"))
    )
    (net (code "55") (name "Net-(LED3-PadC)") (class "Default")
      (node (ref "LED3") (pin "C") (pinfunction "C_C") (pintype "passive"))
      (node (ref "R11") (pin "2") (pinfunction "2_2") (pintype "passive"))
    )
    (net (code "56") (name "Net-(LED4-PadC)") (class "Default")
      (node (ref "LED4") (pin "C") (pinfunction "C_C") (pintype "passive"))
      (node (ref "R12") (pin "2") (pinfunction "2_2") (pintype "passive"))
    )
    (net (code "57") (name "Net-(LED5-PadA)") (class "Default")
      (node (ref "LED5") (pin "A") (pinfunction "A_A") (pintype "passive"))
      (node (ref "U6") (pin "GPIO4") (pinfunction "GPIO4_GPIO4") (pintype "bidirectional"))
    )
    (net (code "58") (name "Net-(LED5-PadC)") (class "Default")
      (node (ref "LED5") (pin "C") (pinfunction "C_C") (pintype "passive"))
      (node (ref "R21") (pin "2") (pinfunction "2_2") (pintype "passive"))
    )
    (net (code "59") (name "Net-(LED6-PadC)") (class "Default")
      (node (ref "LED6") (pin "C") (pinfunction "C_C") (pintype "passive"))
      (node (ref "R25") (pin "2") (pinfunction "2_2") (pintype "passive"))
    )
    (net (code "60") (name "Net-(R14-Pad2)") (class "Default")
      (node (ref "R14") (pin "2") (pinfunction "2_2") (pintype "passive"))
      (node (ref "U6") (pin "GPIO15") (pinfunction "GPIO15_GPIO15") (pintype "bidirectional"))
    )
    (net (code "61") (name "Net-(R30-Pad1)") (class "Default")
      (node (ref "R30") (pin "1") (pinfunction "1_1") (pintype "passive"))
      (node (ref "U6") (pin "CH_PD") (pinfunction "CH_PD_CH_PD") (pintype "bidirectional"))
    )
    (net (code "62") (name "Net-(U$1-CHANNELIN{slash}OUT0)") (class "Default")
      (node (ref "U$1") (pin "9") (pinfunction "CHANNELIN/OUT0_9") (pintype "bidirectional"))
      (node (ref "U1") (pin "1") (pinfunction "1B_1") (pintype "passive"))
    )
    (net (code "63") (name "Net-(U$1-CHANNELIN{slash}OUT1)") (class "Default")
      (node (ref "U$1") (pin "8") (pinfunction "CHANNELIN/OUT1_8") (pintype "bidirectional"))
      (node (ref "U1") (pin "2") (pinfunction "2B_2") (pintype "passive"))
    )
    (net (code "64") (name "Net-(U$1-CHANNELIN{slash}OUT2)") (class "Default")
      (node (ref "U$1") (pin "7") (pinfunction "CHANNELIN/OUT2_7") (pintype "bidirectional"))
      (node (ref "U1") (pin "3") (pinfunction "3B_3") (pintype "passive"))
    )
    (net (code "65") (name "Net-(U$1-CHANNELIN{slash}OUT3)") (class "Default")
      (node (ref "U$1") (pin "6") (pinfunction "CHANNELIN/OUT3_6") (pintype "bidirectional"))
      (node (ref "U1") (pin "4") (pinfunction "4B_4") (pintype "passive"))
    )
    (net (code "66") (name "Net-(U$1-CHANNELIN{slash}OUT4)") (class "Default")
      (node (ref "U$1") (pin "5") (pinfunction "CHANNELIN/OUT4_5") (pintype "bidirectional"))
      (node (ref "U1") (pin "5") (pinfunction "5B_5") (pintype "passive"))
    )
    (net (code "67") (name "Net-(U$1-CHANNELIN{slash}OUT5)") (class "Default")
      (node (ref "U$1") (pin "4") (pinfunction "CHANNELIN/OUT5_4") (pintype "bidirectional"))
      (node (ref "U1") (pin "6") (pinfunction "6B_6") (pintype "passive"))
    )
    (net (code "68") (name "Net-(U$1-CHANNELIN{slash}OUT6)") (class "Default")
      (node (ref "U$1") (pin "3") (pinfunction "CHANNELIN/OUT6_3") (pintype "bidirectional"))
      (node (ref "U1") (pin "7") (pinfunction "7B_7") (pintype "passive"))
    )
    (net (code "69") (name "Net-(U$1-CHANNELIN{slash}OUT7)") (class "Default")
      (node (ref "U$1") (pin "2") (pinfunction "CHANNELIN/OUT7_2") (pintype "bidirectional"))
      (node (ref "U1") (pin "8") (pinfunction "8B_8") (pintype "passive"))
    )
    (net (code "70") (name "Net-(U$1-CHANNELIN{slash}OUT8)") (class "Default")
      (node (ref "U$1") (pin "23") (pinfunction "CHANNELIN/OUT8_23") (pintype "bidirectional"))
      (node (ref "U2") (pin "1") (pinfunction "1B_1") (pintype "passive"))
    )
    (net (code "71") (name "Net-(U$1-CHANNELIN{slash}OUT9)") (class "Default")
      (node (ref "U$1") (pin "22") (pinfunction "CHANNELIN/OUT9_22") (pintype "bidirectional"))
      (node (ref "U2") (pin "2") (pinfunction "2B_2") (pintype "passive"))
    )
    (net (code "72") (name "Net-(U$1-CHANNELIN{slash}OUT10)") (class "Default")
      (node (ref "U$1") (pin "21") (pinfunction "CHANNELIN/OUT10_21") (pintype "bidirectional"))
      (node (ref "U2") (pin "3") (pinfunction "3B_3") (pintype "passive"))
    )
    (net (code "73") (name "Net-(U$1-CHANNELIN{slash}OUT11)") (class "Default")
      (node (ref "U$1") (pin "20") (pinfunction "CHANNELIN/OUT11_20") (pintype "bidirectional"))
      (node (ref "U2") (pin "4") (pinfunction "4B_4") (pintype "passive"))
    )
    (net (code "74") (name "Net-(U$1-CHANNELIN{slash}OUT12)") (class "Default")
      (node (ref "U$1") (pin "19") (pinfunction "CHANNELIN/OUT12_19") (pintype "bidirectional"))
      (node (ref "U2") (pin "5") (pinfunction "5B_5") (pintype "passive"))
    )
    (net (code "75") (name "Net-(U$1-CHANNELIN{slash}OUT13)") (class "Default")
      (node (ref "U$1") (pin "18") (pinfunction "CHANNELIN/OUT13_18") (pintype "bidirectional"))
      (node (ref "U2") (pin "6") (pinfunction "6B_6") (pintype "passive"))
    )
    (net (code "76") (name "Net-(U$1-CHANNELIN{slash}OUT14)") (class "Default")
      (node (ref "U$1") (pin "17") (pinfunction "CHANNELIN/OUT14_17") (pintype "bidirectional"))
      (node (ref "U2") (pin "7") (pinfunction "7B_7") (pintype "passive"))
    )
    (net (code "77") (name "Net-(U$1-CHANNELIN{slash}OUT15)") (class "Default")
      (node (ref "U$1") (pin "16") (pinfunction "CHANNELIN/OUT15_16") (pintype "bidirectional"))
      (node (ref "U2") (pin "8") (pinfunction "8B_8") (pintype "passive"))
    )
    (net (code "78") (name "Net-(U$3-BYP)") (class "Default")
      (node (ref "C2") (pin "1") (pinfunction "1_1") (pintype "passive"))
      (node (ref "U$3") (pin "4") (pinfunction "BYP_4") (pintype "passive"))
    )
    (net (code "79") (name "Net-(U$3-~{SHDN})") (class "Default")
      (node (ref "R1") (pin "1") (pinfunction "1_1") (pintype "passive"))
      (node (ref "U$3") (pin "3") (pinfunction "~{SHDN}_3") (pintype "passive"))
    )
    (net (code "80") (name "Net-(U1-1C)") (class "Default")
      (node (ref "U1") (pin "18") (pinfunction "1C_18") (pintype "passive"))
      (node (ref "X1") (pin "8") (pinfunction "1_8") (pintype "passive"))
    )
    (net (code "81") (name "Net-(U1-2C)") (class "Default")
      (node (ref "U1") (pin "17") (pinfunction "2C_17") (pintype "passive"))
      (node (ref "X1") (pin "7") (pinfunction "1_7") (pintype "passive"))
    )
    (net (code "82") (name "Net-(U1-3C)") (class "Default")
      (node (ref "U1") (pin "16") (pinfunction "3C_16") (pintype "passive"))
      (node (ref "X1") (pin "4") (pinfunction "1_4") (pintype "passive"))
    )
    (net (code "83") (name "Net-(U1-4C)") (class "Default")
      (node (ref "U1") (pin "15") (pinfunction "4C_15") (pintype "passive"))
      (node (ref "X1") (pin "5") (pinfunction "1_5") (pintype "passive"))
    )
    (net (code "84") (name "Net-(U1-5C)") (class "Default")
      (node (ref "U1") (pin "14") (pinfunction "5C_14") (pintype "passive"))
      (node (ref "X1") (pin "6") (pinfunction "1_6") (pintype "passive"))
    )
    (net (code "85") (name "Net-(U1-6C)") (class "Default")
      (node (ref "U1") (pin "13") (pinfunction "6C_13") (pintype "passive"))
      (node (ref "X1") (pin "13") (pinfunction "1_13") (pintype "passive"))
    )
    (net (code "86") (name "Net-(U1-7C)") (class "Default")
      (node (ref "U1") (pin "12") (pinfunction "7C_12") (pintype "passive"))
      (node (ref "X1") (pin "14") (pinfunction "1_14") (pintype "passive"))
    )
    (net (code "87") (name "Net-(U1-8C)") (class "Default")
      (node (ref "U1") (pin "11") (pinfunction "8C_11") (pintype "passive"))
      (node (ref "X1") (pin "15") (pinfunction "1_15") (pintype "passive"))
    )
    (net (code "88") (name "Net-(U2-1C)") (class "Default")
      (node (ref "U2") (pin "18") (pinfunction "1C_18") (pintype "passive"))
      (node (ref "X1") (pin "12") (pinfunction "1_12") (pintype "passive"))
    )
    (net (code "89") (name "Net-(U2-2C)") (class "Default")
      (node (ref "U2") (pin "17") (pinfunction "2C_17") (pintype "passive"))
      (node (ref "X1") (pin "11") (pinfunction "1_11") (pintype "passive"))
    )
    (net (code "90") (name "Net-(U2-3C)") (class "Default")
      (node (ref "U2") (pin "16") (pinfunction "3C_16") (pintype "passive"))
      (node (ref "X1") (pin "10") (pinfunction "1_10") (pintype "passive"))
    )
    (net (code "91") (name "Net-(U2-4C)") (class "Default")
      (node (ref "U2") (pin "15") (pinfunction "4C_15") (pintype "passive"))
      (node (ref "X1") (pin "9") (pinfunction "1_9") (pintype "passive"))
    )
    (net (code "92") (name "Net-(U4-ADECAY)") (class "Default")
      (node (ref "R10") (pin "1") (pinfunction "1_1") (pintype "passive"))
      (node (ref "U4") (pin "3") (pinfunction "ADECAY_3") (pintype "input"))
    )
    (net (code "93") (name "Net-(U4-AISEN)") (class "Default")
      (node (ref "R16") (pin "1") (pinfunction "1_1") (pintype "passive"))
      (node (ref "U4") (pin "5") (pinfunction "AISEN_5") (pintype "bidirectional"))
    )
    (net (code "94") (name "Net-(U4-AOUT1)") (class "Default")
      (node (ref "J3") (pin "4") (pinfunction "4_4") (pintype "passive"))
      (node (ref "J4") (pin "4") (pinfunction "4_4") (pintype "passive"))
      (node (ref "U4") (pin "4") (pinfunction "AOUT1_4") (pintype "output"))
    )
    (net (code "95") (name "Net-(U4-AOUT2)") (class "Default")
      (node (ref "J3") (pin "3") (pinfunction "3_3") (pintype "passive"))
      (node (ref "J4") (pin "3") (pinfunction "3_3") (pintype "passive"))
      (node (ref "U4") (pin "6") (pinfunction "AOUT2_6") (pintype "output"))
    )
    (net (code "96") (name "Net-(U4-BDECAY)") (class "Default")
      (node (ref "R17") (pin "1") (pinfunction "1_1") (pintype "passive"))
      (node (ref "U4") (pin "2") (pinfunction "BDECAY_2") (pintype "input"))
    )
    (net (code "97") (name "Net-(U4-BISEN)") (class "Default")
      (node (ref "R15") (pin "1") (pinfunction "1_1") (pintype "passive"))
      (node (ref "U4") (pin "8") (pinfunction "BISEN_8") (pintype "bidirectional"))
    )
    (net (code "98") (name "Net-(U4-BOUT1)") (class "Default")
      (node (ref "J3") (pin "2") (pinfunction "2_2") (pintype "passive"))
      (node (ref "J4") (pin "1") (pinfunction "1_1") (pintype "passive"))
      (node (ref "U4") (pin "9") (pinfunction "BOUT1_9") (pintype "output"))
    )
    (net (code "99") (name "Net-(U4-BOUT2)") (class "Default")
      (node (ref "J3") (pin "1") (pinfunction "1_1") (pintype "passive"))
      (node (ref "J4") (pin "2") (pinfunction "2_2") (pintype "passive"))
      (node (ref "U4") (pin "7") (pinfunction "BOUT2_7") (pintype "output"))
    )
    (net (code "100") (name "Net-(U4-M0{slash}APHASE)") (class "Default")
      (node (ref "M02") (pin "1") (pinfunction "1_1") (pintype "passive"))
      (node (ref "U4") (pin "13") (pinfunction "M0/APHASE_13") (pintype "input"))
    )
    (net (code "101") (name "Net-(U4-M1)") (class "Default")
      (node (ref "M12") (pin "1") (pinfunction "1_1") (pintype "passive"))
      (node (ref "U4") (pin "14") (pinfunction "M1_14") (pintype "input"))
    )
    (net (code "102") (name "Net-(U4-NFAULT)") (class "Default")
      (node (ref "R18") (pin "1") (pinfunction "1_1") (pintype "passive"))
      (node (ref "U4") (pin "16") (pinfunction "NFAULT_16") (pintype "output"))
    )
    (net (code "103") (name "Net-(U4-NSLEEP)") (class "Default")
      (node (ref "R19") (pin "1") (pinfunction "1_1") (pintype "passive"))
      (node (ref "U4") (pin "1") (pinfunction "NSLEEP_1") (pintype "input"))
    )
    (net (code "104") (name "Net-(U4-VCP)") (class "Default")
      (node (ref "C9") (pin "1") (pinfunction "1_1") (pintype "passive"))
      (node (ref "U4") (pin "17") (pinfunction "VCP_17") (pintype "output"))
    )
    (net (code "105") (name "Net-(U5-ADECAY)") (class "Default")
      (node (ref "R2") (pin "1") (pinfunction "1_1") (pintype "passive"))
      (node (ref "U5") (pin "3") (pinfunction "ADECAY_3") (pintype "input"))
    )
    (net (code "106") (name "Net-(U5-AISEN)") (class "Default")
      (node (ref "R4") (pin "1") (pinfunction "1_1") (pintype "passive"))
      (node (ref "U5") (pin "5") (pinfunction "AISEN_5") (pintype "bidirectional"))
    )
    (net (code "107") (name "Net-(U5-AOUT1)") (class "Default")
      (node (ref "J2") (pin "4") (pinfunction "4_4") (pintype "passive"))
      (node (ref "J5") (pin "4") (pinfunction "4_4") (pintype "passive"))
      (node (ref "U5") (pin "4") (pinfunction "AOUT1_4") (pintype "output"))
    )
    (net (code "108") (name "Net-(U5-AOUT2)") (class "Default")
      (node (ref "J2") (pin "3") (pinfunction "3_3") (pintype "passive"))
      (node (ref "J5") (pin "3") (pinfunction "3_3") (pintype "passive"))
      (node (ref "U5") (pin "6") (pinfunction "AOUT2_6") (pintype "output"))
    )
    (net (code "109") (name "Net-(U5-BDECAY)") (class "Default")
      (node (ref "R5") (pin "1") (pinfunction "1_1") (pintype "passive"))
      (node (ref "U5") (pin "2") (pinfunction "BDECAY_2") (pintype "input"))
    )
    (net (code "110") (name "Net-(U5-BISEN)") (class "Default")
      (node (ref "R3") (pin "1") (pinfunction "1_1") (pintype "passive"))
      (node (ref "U5") (pin "8") (pinfunction "BISEN_8") (pintype "bidirectional"))
    )
    (net (code "111") (name "Net-(U5-BOUT1)") (class "Default")
      (node (ref "J2") (pin "2") (pinfunction "2_2") (pintype "passive"))
      (node (ref "J5") (pin "1") (pinfunction "1_1") (pintype "passive"))
      (node (ref "U5") (pin "9") (pinfunction "BOUT1_9") (pintype "output"))
    )
    (net (code "112") (name "Net-(U5-BOUT2)") (class "Default")
      (node (ref "J2") (pin "1") (pinfunction "1_1") (pintype "passive"))
      (node (ref "J5") (pin "2") (pinfunction "2_2") (pintype "passive"))
      (node (ref "U5") (pin "7") (pinfunction "BOUT2_7") (pintype "output"))
    )
    (net (code "113") (name "Net-(U5-M0{slash}APHASE)") (class "Default")
      (node (ref "M01") (pin "1") (pinfunction "1_1") (pintype "passive"))
      (node (ref "U5") (pin "13") (pinfunction "M0/APHASE_13") (pintype "input"))
    )
    (net (code "114") (name "Net-(U5-M1)") (class "Default")
      (node (ref "M11") (pin "1") (pinfunction "1_1") (pintype "passive"))
      (node (ref "U5") (pin "14") (pinfunction "M1_14") (pintype "input"))
    )
    (net (code "115") (name "Net-(U5-NFAULT)") (class "Default")
      (node (ref "R8") (pin "1") (pinfunction "1_1") (pintype "passive"))
      (node (ref "U5") (pin "16") (pinfunction "NFAULT_16") (pintype "output"))
    )
    (net (code "116") (name "Net-(U5-NSLEEP)") (class "Default")
      (node (ref "R9") (pin "1") (pinfunction "1_1") (pintype "passive"))
      (node (ref "U5") (pin "1") (pinfunction "NSLEEP_1") (pintype "input"))
    )
    (net (code "117") (name "Net-(U5-VCP)") (class "Default")
      (node (ref "C11") (pin "1") (pinfunction "1_1") (pintype "passive"))
      (node (ref "U5") (pin "17") (pinfunction "VCP_17") (pintype "output"))
    )
    (net (code "118") (name "Net-(U7-PB6(XTAL1{slash}TOSC1))") (class "Default")
      (node (ref "U7") (pin "7") (pinfunction "PB6(XTAL1/TOSC1)_7") (pintype "bidirectional"))
      (node (ref "Y1") (pin "1") (pinfunction "1_1") (pintype "passive"))
    )
    (net (code "119") (name "Net-(U7-PB7(XTAL2{slash}TOSC2))") (class "Default")
      (node (ref "U7") (pin "8") (pinfunction "PB7(XTAL2/TOSC2)_8") (pintype "bidirectional"))
      (node (ref "Y1") (pin "3") (pinfunction "3_3") (pintype "passive"))
    )
    (net (code "120") (name "Net-(U7-PD7(AIN1))") (class "Default")
      (node (ref "LED6") (pin "A") (pinfunction "A_A") (pintype "passive"))
      (node (ref "U7") (pin "11") (pinfunction "PD7(AIN1)_11") (pintype "bidirectional"))
    )
    (net (code "121") (name "REF1") (class "Default")
      (node (ref "TM1") (pin "2") (pinfunction "S_2") (pintype "passive"))
      (node (ref "U4") (pin "22") (pinfunction "AVREF_22") (pintype "input"))
      (node (ref "U4") (pin "23") (pinfunction "BVREF_23") (pintype "input"))
    )
    (net (code "122") (name "REF2") (class "Default")
      (node (ref "TM2") (pin "2") (pinfunction "S_2") (pintype "passive"))
      (node (ref "U5") (pin "22") (pinfunction "AVREF_22") (pintype "input"))
      (node (ref "U5") (pin "23") (pinfunction "BVREF_23") (pintype "input"))
    )
    (net (code "123") (name "VCC") (class "Default")
      (node (ref "C21") (pin "1") (pinfunction "1_1") (pintype "passive"))
      (node (ref "C22") (pin "1") (pinfunction "1_1") (pintype "passive"))
      (node (ref "C23") (pin "1") (pinfunction "1_1") (pintype "passive"))
      (node (ref "C24") (pin "+") (pinfunction "+_+") (pintype "passive"))
      (node (ref "C5") (pin "1") (pinfunction "1_1") (pintype "passive"))
      (node (ref "IC1") (pin "6") (pinfunction "VCC_6") (pintype "power_in"))
      (node (ref "J8") (pin "2") (pinfunction "2_2") (pintype "passive"))
      (node (ref "R35") (pin "2") (pinfunction "2_2") (pintype "passive"))
      (node (ref "R40") (pin "P$1") (pinfunction "1_P$1") (pintype "passive"))
      (node (ref "U3") (pin "1") (pinfunction "INPUT_1") (pintype "input"))
      (node (ref "U4") (pin "18") (pinfunction "VM_18") (pintype "power_in"))
      (node (ref "U4") (pin "19") (pinfunction "VM_2_19") (pintype "power_in"))
      (node (ref "U5") (pin "18") (pinfunction "VM_18") (pintype "power_in"))
      (node (ref "U5") (pin "19") (pinfunction "VM_2_19") (pintype "power_in"))
      (node (ref "U8") (pin "1") (pinfunction "1_1") (pintype "passive"))
    )
    (net (code "124") (name "V_BATT") (class "Default")
      (node (ref "J6") (pin "4") (pinfunction "4_4") (pintype "passive"))
      (node (ref "U8") (pin "2") (pinfunction "2_2") (pintype "passive"))
    )
    (net (code "125") (name "unconnected-(J6-Pad2)") (class "Default")
      (node (ref "J6") (pin "2") (pinfunction "2_2") (pintype "passive"))
    )
    (net (code "126") (name "unconnected-(J6-Pad3)") (class "Default")
      (node (ref "J6") (pin "3") (pinfunction "3_3") (pintype "passive"))
    )
    (net (code "127") (name "unconnected-(J10-Pad2)") (class "Default")
      (node (ref "J10") (pin "2") (pinfunction "2_2") (pintype "passive"))
    )
    (net (code "128") (name "unconnected-(U2-5C-Pad14)") (class "Default")
      (node (ref "U2") (pin "14") (pinfunction "5C_14") (pintype "passive"))
    )
    (net (code "129") (name "unconnected-(U2-6C-Pad13)") (class "Default")
      (node (ref "U2") (pin "13") (pinfunction "6C_13") (pintype "passive"))
    )
    (net (code "130") (name "unconnected-(U2-7C-Pad12)") (class "Default")
      (node (ref "U2") (pin "12") (pinfunction "7C_12") (pintype "passive"))
    )
    (net (code "131") (name "unconnected-(U2-8C-Pad11)") (class "Default")
      (node (ref "U2") (pin "11") (pinfunction "8C_11") (pintype "passive"))
    )
    (net (code "132") (name "unconnected-(U6-*GPIO9-PadGPIO9)") (class "Default")
      (node (ref "U6") (pin "GPIO9") (pinfunction "*GPIO9_GPIO9") (pintype "bidirectional"))
    )
    (net (code "133") (name "unconnected-(U6-*GPIO10-PadGPIO10)") (class "Default")
      (node (ref "U6") (pin "GPIO10") (pinfunction "*GPIO10_GPIO10") (pintype "bidirectional"))
    )
    (net (code "134") (name "unconnected-(U6-PadADC)") (class "Default")
      (node (ref "U6") (pin "ADC") (pinfunction "ADC_ADC") (pintype "bidirectional"))
    )
    (net (code "135") (name "unconnected-(U6-PadCS0)") (class "Default")
      (node (ref "U6") (pin "CS0") (pinfunction "CS0_CS0") (pintype "bidirectional"))
    )
    (net (code "136") (name "unconnected-(U6-PadGPIO5)") (class "Default")
      (node (ref "U6") (pin "GPIO5") (pinfunction "GPIO5_GPIO5") (pintype "bidirectional"))
    )
    (net (code "137") (name "unconnected-(U6-PadMISO)") (class "Default")
      (node (ref "U6") (pin "MISO") (pinfunction "MISO_MISO") (pintype "bidirectional"))
    )
    (net (code "138") (name "unconnected-(U6-PadMOSI)") (class "Default")
      (node (ref "U6") (pin "MOSI") (pinfunction "MOSI_MOSI") (pintype "bidirectional"))
    )
    (net (code "139") (name "unconnected-(U6-PadSCLK)") (class "Default")
      (node (ref "U6") (pin "SCLK") (pinfunction "SCLK_SCLK") (pintype "bidirectional"))
    )
    (net (code "140") (name "unconnected-(U7-ADC6-Pad19)") (class "Default")
      (node (ref "U7") (pin "19") (pinfunction "ADC6_19") (pintype "bidirectional"))
    )
    (net (code "141") (name "unconnected-(U7-ADC7-Pad22)") (class "Default")
      (node (ref "U7") (pin "22") (pinfunction "ADC7_22") (pintype "bidirectional"))
    )
    (net (code "142") (name "unconnected-(U7-AREF-Pad20)") (class "Default")
      (node (ref "U7") (pin "20") (pinfunction "AREF_20") (pintype "bidirectional"))
    )
    (net (code "143") (name "unconnected-(U7-PC5(ADC5{slash}SCL)-Pad28)") (class "Default")
      (node (ref "U7") (pin "28") (pinfunction "PC5(ADC5/SCL)_28") (pintype "bidirectional"))
    )
    (net (code "144") (name "unconnected-(U8-Pad3)") (class "Default")
      (node (ref "U8") (pin "3") (pinfunction "3_3") (pintype "passive"))
    )
    (net (code "145") (name "unconnected-(X1-Pad1)") (class "Default")
      (node (ref "X1") (pin "1") (pinfunction "1_1") (pintype "passive"))
    )
    (net (code "146") (name "unconnected-(X1I-1-Pad2)") (class "Default")
      (node (ref "X1") (pin "2") (pinfunction "1_2") (pintype "passive"))
    )
  )
)
